# dasblinkenhat-controller-mk-2_0.net
KiCad netlist of a schematic drawn in EAGLE
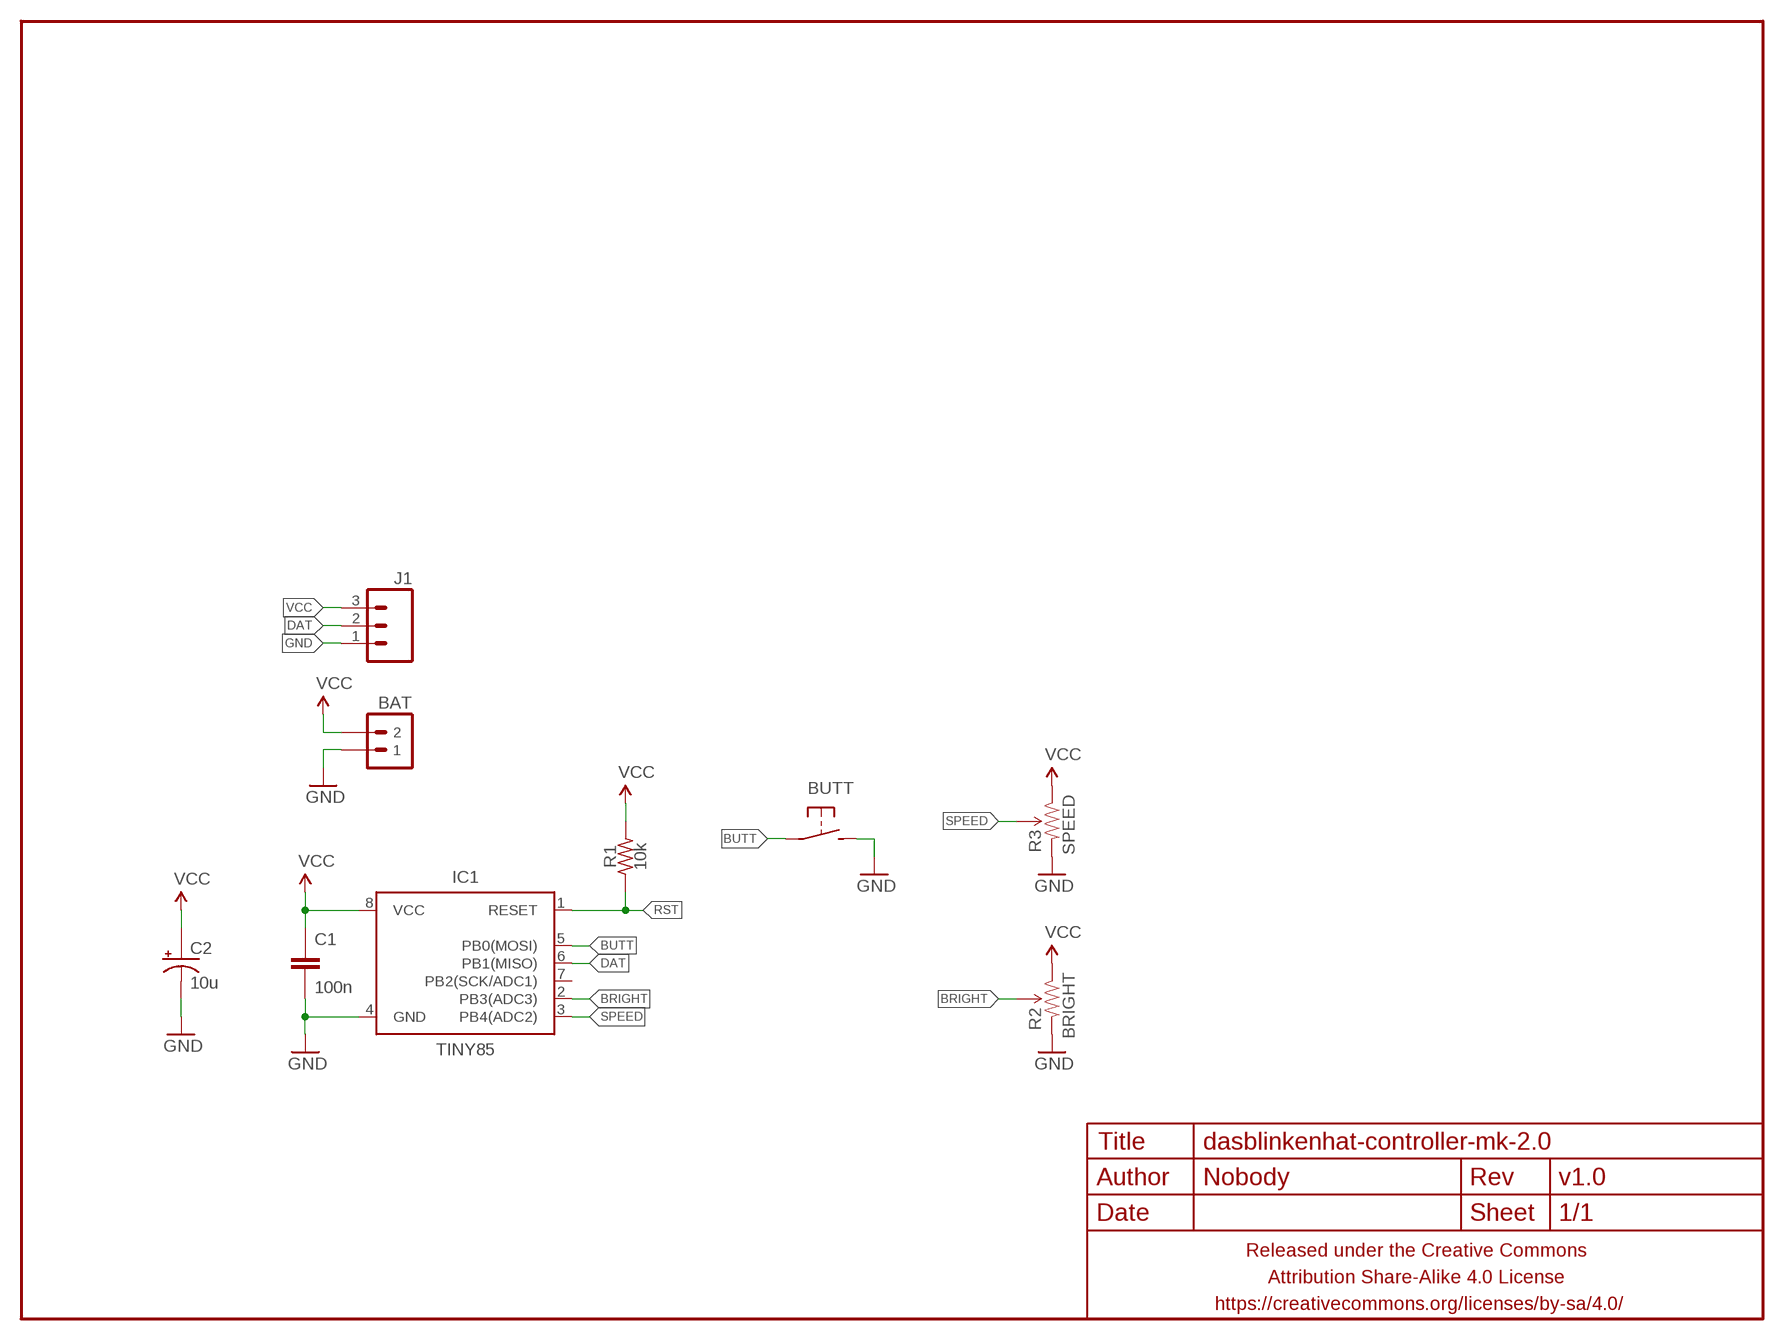
[diagram p0: schematic, sheet 1]

(export (version "E")
  (design (tool "Eeschema 10.0.6"))
  (components
    (comp (ref "BAT")
      (value "M02JST-PTH-RA-R+")
      (footprint "eagle-import:JST-2-PH-RA-PTH-R+")
      (libsource (lib "eagle-import") (part "M02JST-PTH-RA-R+"))
    )
    (comp (ref "BUTT")
      (value "DTS-6MM")
      (footprint "eagle-import:DTS-6-SMALL-PADS")
      (libsource (lib "eagle-import") (part "SPST-NO-TACT6MM-PTH-SMALL-PADS"))
    )
    (comp (ref "C1")
      (value "100n")
      (footprint "eagle-import:C025-024X044")
      (libsource (lib "eagle-import") (part "CAPACITOR-CERAMIC025-024X044"))
    )
    (comp (ref "C2")
      (value "10u")
      (footprint "eagle-import:E2-5")
      (libsource (lib "eagle-import") (part "CAPACITOR-POLARIZEDE2-5"))
    )
    (comp (ref "FRAME1")
      (value "FRAME-LETTERNO_PACKAGE")
      (footprint "eagle-import:DUMMY")
      (fields (field (name "VERSION") "v1.0") (field (name "DESIGNER") "Nobody"))
      (libsource (lib "eagle-import") (part "FRAME-LETTERNO_PACKAGE"))
    )
    (comp (ref "IC1")
      (value "TINY85")
      (footprint "eagle-import:DIP08")
      (libsource (lib "eagle-import") (part "ATTINY45TINY85-20-DIP"))
    )
    (comp (ref "J1")
      (value "M03JST-XH-RA-PTH")
      (footprint "eagle-import:JST-3-XH-RA-PTH")
      (libsource (lib "eagle-import") (part "M03JST-XH-RA-PTH"))
    )
    (comp (ref "R1")
      (value "10k")
      (footprint "eagle-import:RESISTOR-AXIAL-PTH-5.08MM")
      (libsource (lib "eagle-import") (part "RESISTORPTH-AXIAL-5.08MM"))
    )
    (comp (ref "R2")
      (value "BRIGHT")
      (footprint "eagle-import:TRIM_POT_PTH2")
      (libsource (lib "eagle-import") (part "TRIMPOTPTH2"))
    )
    (comp (ref "R3")
      (value "SPEED")
      (footprint "eagle-import:TRIM_POT_PTH2")
      (libsource (lib "eagle-import") (part "TRIMPOTPTH2"))
    )
  )
  (nets
    (net (code "1") (name "BRIGHT") (class "Default")
      (node (ref "IC1") (pin "2") (pinfunction "PB3(ADC3)_2") (pintype "bidirectional"))
      (node (ref "R2") (pin "2") (pinfunction "WIPER_2") (pintype "passive"))
    )
    (net (code "2") (name "BUTT") (class "Default")
      (node (ref "BUTT") (pin "1") (pinfunction "1_1") (pintype "passive"))
      (node (ref "BUTT") (pin "2") (pinfunction "1_2") (pintype "passive"))
      (node (ref "IC1") (pin "5") (pinfunction "PB0(MOSI)_5") (pintype "bidirectional"))
    )
    (net (code "3") (name "DAT") (class "Default")
      (node (ref "IC1") (pin "6") (pinfunction "PB1(MISO)_6") (pintype "bidirectional"))
      (node (ref "J1") (pin "2") (pinfunction "2_2") (pintype "passive"))
    )
    (net (code "4") (name "GND") (class "Default")
      (node (ref "BAT") (pin "1") (pinfunction "1_1") (pintype "passive"))
      (node (ref "BUTT") (pin "3") (pinfunction "2_3") (pintype "passive"))
      (node (ref "BUTT") (pin "4") (pinfunction "2_4") (pintype "passive"))
      (node (ref "C1") (pin "2") (pinfunction "2_2") (pintype "passive"))
      (node (ref "C2") (pin "-") (pinfunction "-_-") (pintype "passive"))
      (node (ref "IC1") (pin "4") (pinfunction "GND_4") (pintype "bidirectional"))
      (node (ref "J1") (pin "1") (pinfunction "1_1") (pintype "passive"))
      (node (ref "R2") (pin "3") (pinfunction "CW_3") (pintype "passive"))
      (node (ref "R3") (pin "3") (pinfunction "CW_3") (pintype "passive"))
    )
    (net (code "5") (name "RST") (class "Default")
      (node (ref "IC1") (pin "1") (pinfunction "RESET_1") (pintype "bidirectional"))
      (node (ref "R1") (pin "P$1") (pinfunction "1_P$1") (pintype "passive"))
    )
    (net (code "6") (name "SPEED") (class "Default")
      (node (ref "IC1") (pin "3") (pinfunction "PB4(ADC2)_3") (pintype "bidirectional"))
      (node (ref "R3") (pin "2") (pinfunction "WIPER_2") (pintype "passive"))
    )
    (net (code "7") (name "VCC") (class "Default")
      (node (ref "BAT") (pin "2") (pinfunction "2_2") (pintype "passive"))
      (node (ref "C1") (pin "1") (pinfunction "1_1") (pintype "passive"))
      (node (ref "C2") (pin "+") (pinfunction "+_+") (pintype "passive"))
      (node (ref "IC1") (pin "8") (pinfunction "VCC_8") (pintype "bidirectional"))
      (node (ref "J1") (pin "3") (pinfunction "3_3") (pintype "passive"))
      (node (ref "R1") (pin "P$2") (pinfunction "2_P$2") (pintype "passive"))
      (node (ref "R2") (pin "1") (pinfunction "CCW_1") (pintype "passive"))
      (node (ref "R3") (pin "1") (pinfunction "CCW_1") (pintype "passive"))
    )
    (net (code "8") (name "unconnected-(IC1-PB2(SCK{slash}ADC1)-Pad7)") (class "Default")
      (node (ref "IC1") (pin "7") (pinfunction "PB2(SCK/ADC1)_7") (pintype "bidirectional"))
    )
  )
)
